# Schema_2.net
KiCad netlist of a schematic drawn in EAGLE
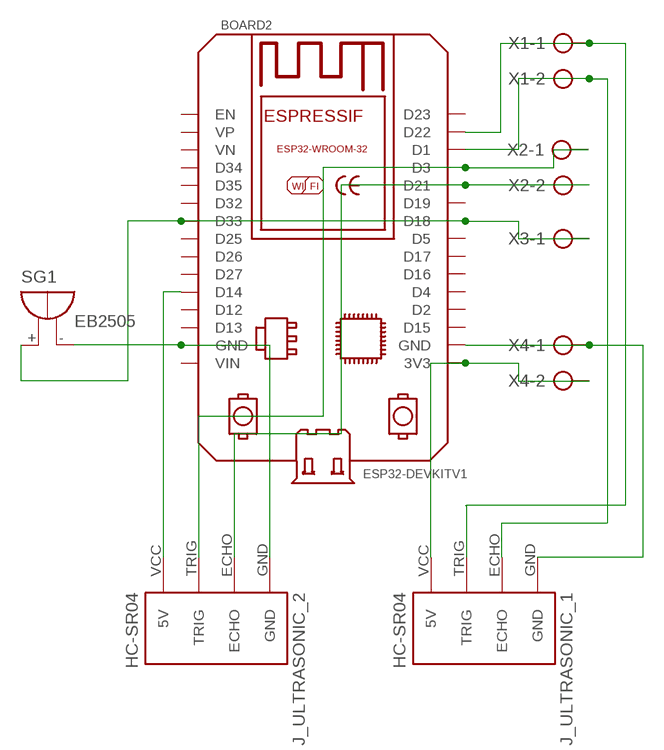
[diagram p0: schematic, sheet 1]

(export (version "E")
  (design (tool "Eeschema 10.0.6"))
  (components
    (comp (ref "BOARD2")
      (value "ESP32DEVKITV1SHRIDATTDUDHAT")
      (footprint "eagle-import:ESP32-DEVKITV1")
      (libsource (lib "eagle-import") (part "ESP32DEVKITV1SHRIDATTDUDHAT"))
    )
    (comp (ref "J_ULTRASONIC_1")
      (value "HC-SR04")
      (footprint "eagle-import:HC-SR04_FOOTPRINT")
      (libsource (lib "eagle-import") (part "HC-SR04"))
    )
    (comp (ref "J_ULTRASONIC_2")
      (value "HC-SR04")
      (footprint "eagle-import:HC-SR04_FOOTPRINT")
      (libsource (lib "eagle-import") (part "HC-SR04"))
    )
    (comp (ref "SG1")
      (value "EB2505")
      (footprint "eagle-import:EB2505")
      (libsource (lib "eagle-import") (part "EB2505"))
    )
    (comp (ref "X1")
      (value "AK300/2")
      (footprint "eagle-import:AK300_2")
      (libsource (lib "eagle-import") (part "AK300/2"))
    )
    (comp (ref "X2")
      (value "AK300/2")
      (footprint "eagle-import:AK300_2")
      (libsource (lib "eagle-import") (part "AK300/2"))
    )
    (comp (ref "X3")
      (value "AK300/2")
      (footprint "eagle-import:AK300_2")
      (libsource (lib "eagle-import") (part "AK300/2"))
    )
    (comp (ref "X4")
      (value "AK300/2")
      (footprint "eagle-import:AK300_2")
      (libsource (lib "eagle-import") (part "AK300/2"))
    )
  )
  (nets
    (net (code "1") (name "Net-(BOARD2-PadGND)") (class "Default")
      (node (ref "BOARD2") (pin "GND") (pinfunction "GND_GND") (pintype "bidirectional"))
      (node (ref "J_ULTRASONIC_2") (pin "GND") (pinfunction "GND_GND") (pintype "bidirectional"))
      (node (ref "SG1") (pin "-") (pinfunction "-_-") (pintype "passive"))
    )
    (net (code "2") (name "Net-(J_ULTRASONIC_1-5V)") (class "Default")
      (node (ref "BOARD2") (pin "3V3") (pinfunction "3V3_3V3") (pintype "bidirectional"))
      (node (ref "J_ULTRASONIC_1") (pin "VCC") (pinfunction "5V_VCC") (pintype "bidirectional"))
      (node (ref "X4") (pin "2") (pinfunction "KL_2") (pintype "passive"))
    )
    (net (code "3") (name "Net-(J_ULTRASONIC_2-5V)") (class "Default")
      (node (ref "BOARD2") (pin "D14") (pinfunction "D14_D14") (pintype "bidirectional"))
      (node (ref "J_ULTRASONIC_2") (pin "VCC") (pinfunction "5V_VCC") (pintype "bidirectional"))
    )
    (net (code "4") (name "Net-(X1A-KL)") (class "Default")
      (node (ref "BOARD2") (pin "D22") (pinfunction "D22_D22") (pintype "bidirectional"))
      (node (ref "J_ULTRASONIC_1") (pin "TRIG") (pinfunction "TRIG_TRIG") (pintype "bidirectional"))
      (node (ref "X1") (pin "1") (pinfunction "KL_1") (pintype "passive"))
    )
    (net (code "5") (name "Net-(X1B-KL)") (class "Default")
      (node (ref "BOARD2") (pin "D1") (pinfunction "D1_D1") (pintype "bidirectional"))
      (node (ref "J_ULTRASONIC_1") (pin "ECHO") (pinfunction "ECHO_ECHO") (pintype "bidirectional"))
      (node (ref "X1") (pin "2") (pinfunction "KL_2") (pintype "passive"))
    )
    (net (code "6") (name "Net-(X2A-KL)") (class "Default")
      (node (ref "BOARD2") (pin "D3") (pinfunction "D3_D3") (pintype "bidirectional"))
      (node (ref "J_ULTRASONIC_2") (pin "TRIG") (pinfunction "TRIG_TRIG") (pintype "bidirectional"))
      (node (ref "X2") (pin "1") (pinfunction "KL_1") (pintype "passive"))
    )
    (net (code "7") (name "Net-(X2B-KL)") (class "Default")
      (node (ref "BOARD2") (pin "D21") (pinfunction "D21_D21") (pintype "bidirectional"))
      (node (ref "J_ULTRASONIC_2") (pin "ECHO") (pinfunction "ECHO_ECHO") (pintype "bidirectional"))
      (node (ref "X2") (pin "2") (pinfunction "KL_2") (pintype "passive"))
    )
    (net (code "8") (name "Net-(X3A-KL)") (class "Default")
      (node (ref "BOARD2") (pin "D18") (pinfunction "D18_D18") (pintype "bidirectional"))
      (node (ref "BOARD2") (pin "D33") (pinfunction "D33_D33") (pintype "bidirectional"))
      (node (ref "SG1") (pin "+") (pinfunction "+_+") (pintype "passive"))
      (node (ref "X3") (pin "1") (pinfunction "KL_1") (pintype "passive"))
    )
    (net (code "9") (name "Net-(X4A-KL)") (class "Default")
      (node (ref "BOARD2") (pin "GND@1") (pinfunction "GND_GND@1") (pintype "bidirectional"))
      (node (ref "J_ULTRASONIC_1") (pin "GND") (pinfunction "GND_GND") (pintype "bidirectional"))
      (node (ref "X4") (pin "1") (pinfunction "KL_1") (pintype "passive"))
    )
    (net (code "10") (name "unconnected-(BOARD2-PadD2)") (class "Default")
      (node (ref "BOARD2") (pin "D2") (pinfunction "D2_D2") (pintype "bidirectional"))
    )
    (net (code "11") (name "unconnected-(BOARD2-PadD4)") (class "Default")
      (node (ref "BOARD2") (pin "D4") (pinfunction "D4_D4") (pintype "bidirectional"))
    )
    (net (code "12") (name "unconnected-(BOARD2-PadD5)") (class "Default")
      (node (ref "BOARD2") (pin "D5") (pinfunction "D5_D5") (pintype "bidirectional"))
    )
    (net (code "13") (name "unconnected-(BOARD2-PadD12)") (class "Default")
      (node (ref "BOARD2") (pin "D12") (pinfunction "D12_D12") (pintype "bidirectional"))
    )
    (net (code "14") (name "unconnected-(BOARD2-PadD13)") (class "Default")
      (node (ref "BOARD2") (pin "D13") (pinfunction "D13_D13") (pintype "bidirectional"))
    )
    (net (code "15") (name "unconnected-(BOARD2-PadD15)") (class "Default")
      (node (ref "BOARD2") (pin "D15") (pinfunction "D15_D15") (pintype "bidirectional"))
    )
    (net (code "16") (name "unconnected-(BOARD2-PadD16)") (class "Default")
      (node (ref "BOARD2") (pin "D16") (pinfunction "D16_D16") (pintype "bidirectional"))
    )
    (net (code "17") (name "unconnected-(BOARD2-PadD17)") (class "Default")
      (node (ref "BOARD2") (pin "D17") (pinfunction "D17_D17") (pintype "bidirectional"))
    )
    (net (code "18") (name "unconnected-(BOARD2-PadD19)") (class "Default")
      (node (ref "BOARD2") (pin "D19") (pinfunction "D19_D19") (pintype "bidirectional"))
    )
    (net (code "19") (name "unconnected-(BOARD2-PadD23)") (class "Default")
      (node (ref "BOARD2") (pin "D23") (pinfunction "D23_D23") (pintype "bidirectional"))
    )
    (net (code "20") (name "unconnected-(BOARD2-PadD25)") (class "Default")
      (node (ref "BOARD2") (pin "D25") (pinfunction "D25_D25") (pintype "bidirectional"))
    )
    (net (code "21") (name "unconnected-(BOARD2-PadD26)") (class "Default")
      (node (ref "BOARD2") (pin "D26") (pinfunction "D26_D26") (pintype "bidirectional"))
    )
    (net (code "22") (name "unconnected-(BOARD2-PadD27)") (class "Default")
      (node (ref "BOARD2") (pin "D27") (pinfunction "D27_D27") (pintype "bidirectional"))
    )
    (net (code "23") (name "unconnected-(BOARD2-PadD32)") (class "Default")
      (node (ref "BOARD2") (pin "D32") (pinfunction "D32_D32") (pintype "bidirectional"))
    )
    (net (code "24") (name "unconnected-(BOARD2-PadD34)") (class "Default")
      (node (ref "BOARD2") (pin "D34") (pinfunction "D34_D34") (pintype "bidirectional"))
    )
    (net (code "25") (name "unconnected-(BOARD2-PadD35)") (class "Default")
      (node (ref "BOARD2") (pin "D35") (pinfunction "D35_D35") (pintype "bidirectional"))
    )
    (net (code "26") (name "unconnected-(BOARD2-PadEN)") (class "Default")
      (node (ref "BOARD2") (pin "EN") (pinfunction "EN_EN") (pintype "bidirectional"))
    )
    (net (code "27") (name "unconnected-(BOARD2-PadVIN)") (class "Default")
      (node (ref "BOARD2") (pin "VIN") (pinfunction "VIN_VIN") (pintype "bidirectional"))
    )
    (net (code "28") (name "unconnected-(BOARD2-PadVN)") (class "Default")
      (node (ref "BOARD2") (pin "VN") (pinfunction "VN_VN") (pintype "bidirectional"))
    )
    (net (code "29") (name "unconnected-(BOARD2-PadVP)") (class "Default")
      (node (ref "BOARD2") (pin "VP") (pinfunction "VP_VP") (pintype "bidirectional"))
    )
  )
)
